# LM35_Remote.net
KiCad netlist of a schematic drawn in EAGLE
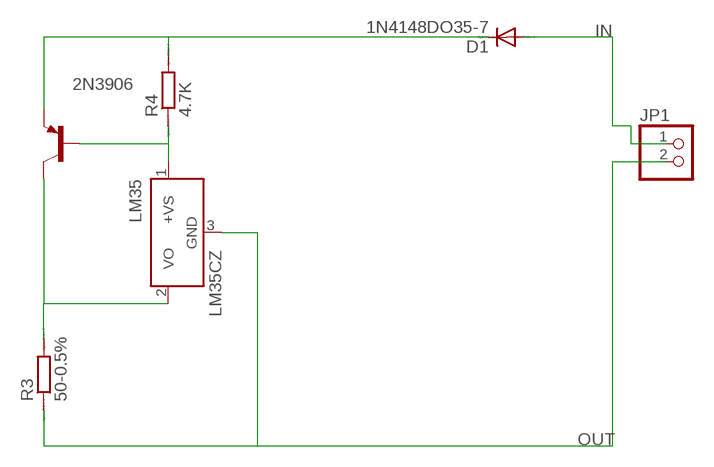
[diagram p0: schematic, sheet 1]

(export (version "E")
  (design (tool "Eeschema 10.0.6"))
  (components
    (comp (ref "2N3906")
      (value "2N3906-PNP-TO92-EBC")
      (footprint "eagle-import:TO92-EBC")
      (libsource (lib "eagle-import") (part "-PNP-TO92-EBC2N3906"))
    )
    (comp (ref "D1")
      (value "1N4148DO35-7")
      (footprint "eagle-import:DO35-7")
      (libsource (lib "eagle-import") (part "1N4148DO35-7"))
    )
    (comp (ref "JP1")
      (value "PINHD-1X2")
      (footprint "eagle-import:1X02")
      (libsource (lib "eagle-import") (part "PINHD-1X2"))
    )
    (comp (ref "LM35")
      (value "LM35CZ")
      (footprint "eagle-import:TO92")
      (libsource (lib "eagle-import") (part "LM35CZ"))
    )
    (comp (ref "R3")
      (value "50-0.5%")
      (footprint "eagle-import:0207_7")
      (libsource (lib "eagle-import") (part "R-EU_0207_7"))
    )
    (comp (ref "R4")
      (value "4.7K")
      (footprint "eagle-import:0207_7")
      (libsource (lib "eagle-import") (part "R-EU_0207_7"))
    )
  )
  (nets
    (net (code "1") (name "/IN") (class "Default")
      (node (ref "D1") (pin "A") (pinfunction "A_A") (pintype "passive"))
      (node (ref "JP1") (pin "1") (pinfunction "1_1") (pintype "passive"))
    )
    (net (code "2") (name "/OUT") (class "Default")
      (node (ref "JP1") (pin "2") (pinfunction "2_2") (pintype "passive"))
      (node (ref "LM35") (pin "3") (pinfunction "GND_3") (pintype "power_in"))
      (node (ref "R3") (pin "1") (pinfunction "1_1") (pintype "passive"))
    )
    (net (code "3") (name "Net-(2N3906-PadE)") (class "Default")
      (node (ref "2N3906") (pin "E") (pinfunction "E_E") (pintype "passive"))
      (node (ref "D1") (pin "C") (pinfunction "C_C") (pintype "passive"))
      (node (ref "R4") (pin "2") (pinfunction "2_2") (pintype "passive"))
    )
    (net (code "4") (name "Net-(LM35-+VS)") (class "Default")
      (node (ref "2N3906") (pin "B") (pinfunction "B_B") (pintype "passive"))
      (node (ref "LM35") (pin "1") (pinfunction "+VS_1") (pintype "input"))
      (node (ref "R4") (pin "1") (pinfunction "1_1") (pintype "passive"))
    )
    (net (code "5") (name "Net-(LM35-VO)") (class "Default")
      (node (ref "2N3906") (pin "C") (pinfunction "C_C") (pintype "passive"))
      (node (ref "LM35") (pin "2") (pinfunction "VO_2") (pintype "input"))
      (node (ref "R3") (pin "2") (pinfunction "2_2") (pintype "passive"))
    )
  )
)
